# RGB_i2c_LED_v2.net
KiCad netlist of a schematic drawn in EAGLE
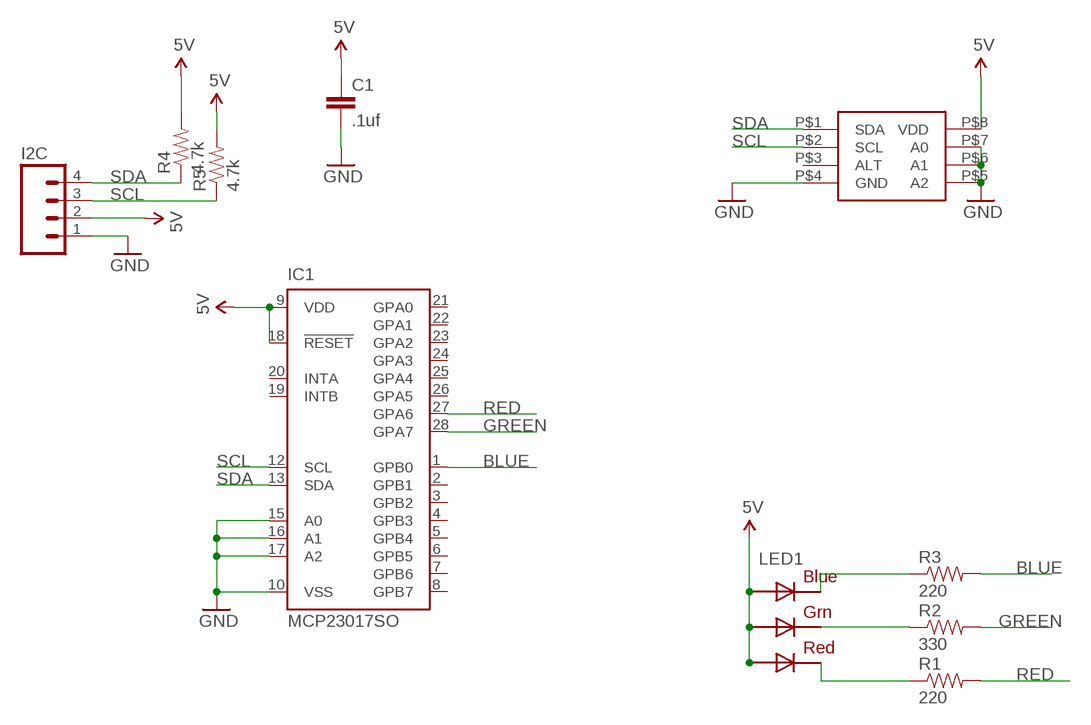
[diagram p0: schematic, sheet 1]

(export (version "E")
  (design (tool "Eeschema 10.0.6"))
  (components
    (comp (ref "C1")
      (value ".1uf")
      (footprint "eagle-import:0805")
      (libsource (lib "eagle-import") (part "CAP0805"))
    )
    (comp (ref "I2C")
      (value "M04LOCK")
      (footprint "eagle-import:1X04_LOCK")
      (libsource (lib "eagle-import") (part "M04LOCK"))
    )
    (comp (ref "IC1")
      (value "MCP23017SO")
      (footprint "eagle-import:SO28W")
      (libsource (lib "eagle-import") (part "MCP23017SO"))
    )
    (comp (ref "IC2")
      (value "MCP9808")
      (footprint "eagle-import:MSOP8")
      (libsource (lib "eagle-import") (part "MCP9808"))
    )
    (comp (ref "LED1")
      (value "RGBLED5050")
      (footprint "eagle-import:RGBLED5050")
      (libsource (lib "eagle-import") (part "RGBLED5050"))
    )
    (comp (ref "R1")
      (value "220")
      (footprint "eagle-import:0805")
      (libsource (lib "eagle-import") (part "RESISTOR0805-RES"))
    )
    (comp (ref "R2")
      (value "330")
      (footprint "eagle-import:0805")
      (libsource (lib "eagle-import") (part "RESISTOR0805-RES"))
    )
    (comp (ref "R3")
      (value "220")
      (footprint "eagle-import:0805")
      (libsource (lib "eagle-import") (part "RESISTOR0805-RES"))
    )
    (comp (ref "R4")
      (value "4.7k")
      (footprint "eagle-import:0805")
      (libsource (lib "eagle-import") (part "RESISTOR0805-RES"))
    )
    (comp (ref "R5")
      (value "4.7k")
      (footprint "eagle-import:0805")
      (libsource (lib "eagle-import") (part "RESISTOR0805-RES"))
    )
  )
  (nets
    (net (code "1") (name "/BLUE") (class "Default")
      (node (ref "IC1") (pin "1") (pinfunction "GPB0_1") (pintype "bidirectional"))
      (node (ref "R3") (pin "2") (pinfunction "2_2") (pintype "passive"))
    )
    (net (code "2") (name "/GREEN") (class "Default")
      (node (ref "IC1") (pin "28") (pinfunction "GPA7_28") (pintype "bidirectional"))
      (node (ref "R2") (pin "2") (pinfunction "2_2") (pintype "passive"))
    )
    (net (code "3") (name "/RED") (class "Default")
      (node (ref "IC1") (pin "27") (pinfunction "GPA6_27") (pintype "bidirectional"))
      (node (ref "R1") (pin "2") (pinfunction "2_2") (pintype "passive"))
    )
    (net (code "4") (name "/SCL") (class "Default")
      (node (ref "I2C") (pin "3") (pinfunction "3_3") (pintype "passive"))
      (node (ref "IC1") (pin "12") (pinfunction "SCL_12") (pintype "input"))
      (node (ref "IC2") (pin "P$2") (pinfunction "SCL_P$2") (pintype "bidirectional"))
      (node (ref "R5") (pin "1") (pinfunction "1_1") (pintype "passive"))
    )
    (net (code "5") (name "/SDA") (class "Default")
      (node (ref "I2C") (pin "4") (pinfunction "4_4") (pintype "passive"))
      (node (ref "IC1") (pin "13") (pinfunction "SDA_13") (pintype "bidirectional"))
      (node (ref "IC2") (pin "P$1") (pinfunction "SDA_P$1") (pintype "bidirectional"))
      (node (ref "R4") (pin "1") (pinfunction "1_1") (pintype "passive"))
    )
    (net (code "6") (name "5V") (class "Default")
      (node (ref "C1") (pin "1") (pinfunction "1_1") (pintype "passive"))
      (node (ref "I2C") (pin "2") (pinfunction "2_2") (pintype "passive"))
      (node (ref "IC1") (pin "18") (pinfunction "~{RESET}_18") (pintype "input"))
      (node (ref "IC1") (pin "9") (pinfunction "VDD_9") (pintype "power_in"))
      (node (ref "IC2") (pin "P$8") (pinfunction "VDD_P$8") (pintype "bidirectional"))
      (node (ref "LED1") (pin "4") (pinfunction "GREEN_A_4") (pintype "bidirectional"))
      (node (ref "LED1") (pin "5") (pinfunction "RED_A_5") (pintype "bidirectional"))
      (node (ref "LED1") (pin "6") (pinfunction "BLUE_A_6") (pintype "bidirectional"))
      (node (ref "R4") (pin "2") (pinfunction "2_2") (pintype "passive"))
      (node (ref "R5") (pin "2") (pinfunction "2_2") (pintype "passive"))
    )
    (net (code "7") (name "GND") (class "Default")
      (node (ref "C1") (pin "2") (pinfunction "2_2") (pintype "passive"))
      (node (ref "I2C") (pin "1") (pinfunction "1_1") (pintype "passive"))
      (node (ref "IC1") (pin "10") (pinfunction "VSS_10") (pintype "power_in"))
      (node (ref "IC1") (pin "15") (pinfunction "A0_15") (pintype "input"))
      (node (ref "IC1") (pin "16") (pinfunction "A1_16") (pintype "input"))
      (node (ref "IC1") (pin "17") (pinfunction "A2_17") (pintype "input"))
      (node (ref "IC2") (pin "P$4") (pinfunction "GND_P$4") (pintype "bidirectional"))
      (node (ref "IC2") (pin "P$5") (pinfunction "A2_P$5") (pintype "bidirectional"))
      (node (ref "IC2") (pin "P$6") (pinfunction "A1_P$6") (pintype "bidirectional"))
      (node (ref "IC2") (pin "P$7") (pinfunction "A0_P$7") (pintype "bidirectional"))
    )
    (net (code "8") (name "Net-(LED1-BLUE_C)") (class "Default")
      (node (ref "LED1") (pin "3") (pinfunction "BLUE_C_3") (pintype "bidirectional"))
      (node (ref "R3") (pin "1") (pinfunction "1_1") (pintype "passive"))
    )
    (net (code "9") (name "Net-(LED1-GREEN_C)") (class "Default")
      (node (ref "LED1") (pin "1") (pinfunction "GREEN_C_1") (pintype "bidirectional"))
      (node (ref "R2") (pin "1") (pinfunction "1_1") (pintype "passive"))
    )
    (net (code "10") (name "Net-(LED1-RED_C)") (class "Default")
      (node (ref "LED1") (pin "2") (pinfunction "RED_C_2") (pintype "bidirectional"))
      (node (ref "R1") (pin "1") (pinfunction "1_1") (pintype "passive"))
    )
    (net (code "11") (name "unconnected-(IC1-GPA0-Pad21)") (class "Default")
      (node (ref "IC1") (pin "21") (pinfunction "GPA0_21") (pintype "bidirectional"))
    )
    (net (code "12") (name "unconnected-(IC1-GPA1-Pad22)") (class "Default")
      (node (ref "IC1") (pin "22") (pinfunction "GPA1_22") (pintype "bidirectional"))
    )
    (net (code "13") (name "unconnected-(IC1-GPA2-Pad23)") (class "Default")
      (node (ref "IC1") (pin "23") (pinfunction "GPA2_23") (pintype "bidirectional"))
    )
    (net (code "14") (name "unconnected-(IC1-GPA3-Pad24)") (class "Default")
      (node (ref "IC1") (pin "24") (pinfunction "GPA3_24") (pintype "bidirectional"))
    )
    (net (code "15") (name "unconnected-(IC1-GPA4-Pad25)") (class "Default")
      (node (ref "IC1") (pin "25") (pinfunction "GPA4_25") (pintype "bidirectional"))
    )
    (net (code "16") (name "unconnected-(IC1-GPA5-Pad26)") (class "Default")
      (node (ref "IC1") (pin "26") (pinfunction "GPA5_26") (pintype "bidirectional"))
    )
    (net (code "17") (name "unconnected-(IC1-GPB1-Pad2)") (class "Default")
      (node (ref "IC1") (pin "2") (pinfunction "GPB1_2") (pintype "bidirectional"))
    )
    (net (code "18") (name "unconnected-(IC1-GPB2-Pad3)") (class "Default")
      (node (ref "IC1") (pin "3") (pinfunction "GPB2_3") (pintype "bidirectional"))
    )
    (net (code "19") (name "unconnected-(IC1-GPB3-Pad4)") (class "Default")
      (node (ref "IC1") (pin "4") (pinfunction "GPB3_4") (pintype "bidirectional"))
    )
    (net (code "20") (name "unconnected-(IC1-GPB4-Pad5)") (class "Default")
      (node (ref "IC1") (pin "5") (pinfunction "GPB4_5") (pintype "bidirectional"))
    )
    (net (code "21") (name "unconnected-(IC1-GPB5-Pad6)") (class "Default")
      (node (ref "IC1") (pin "6") (pinfunction "GPB5_6") (pintype "bidirectional"))
    )
    (net (code "22") (name "unconnected-(IC1-GPB6-Pad7)") (class "Default")
      (node (ref "IC1") (pin "7") (pinfunction "GPB6_7") (pintype "bidirectional"))
    )
    (net (code "23") (name "unconnected-(IC1-GPB7-Pad8)") (class "Default")
      (node (ref "IC1") (pin "8") (pinfunction "GPB7_8") (pintype "bidirectional"))
    )
    (net (code "24") (name "unconnected-(IC1-INTA-Pad20)") (class "Default")
      (node (ref "IC1") (pin "20") (pinfunction "INTA_20") (pintype "output"))
    )
    (net (code "25") (name "unconnected-(IC1-INTB-Pad19)") (class "Default")
      (node (ref "IC1") (pin "19") (pinfunction "INTB_19") (pintype "output"))
    )
    (net (code "26") (name "unconnected-(IC2-ALT-PadP$3)") (class "Default")
      (node (ref "IC2") (pin "P$3") (pinfunction "ALT_P$3") (pintype "bidirectional"))
    )
  )
)
